# irisc.net
KiCad netlist of a schematic drawn in EAGLE
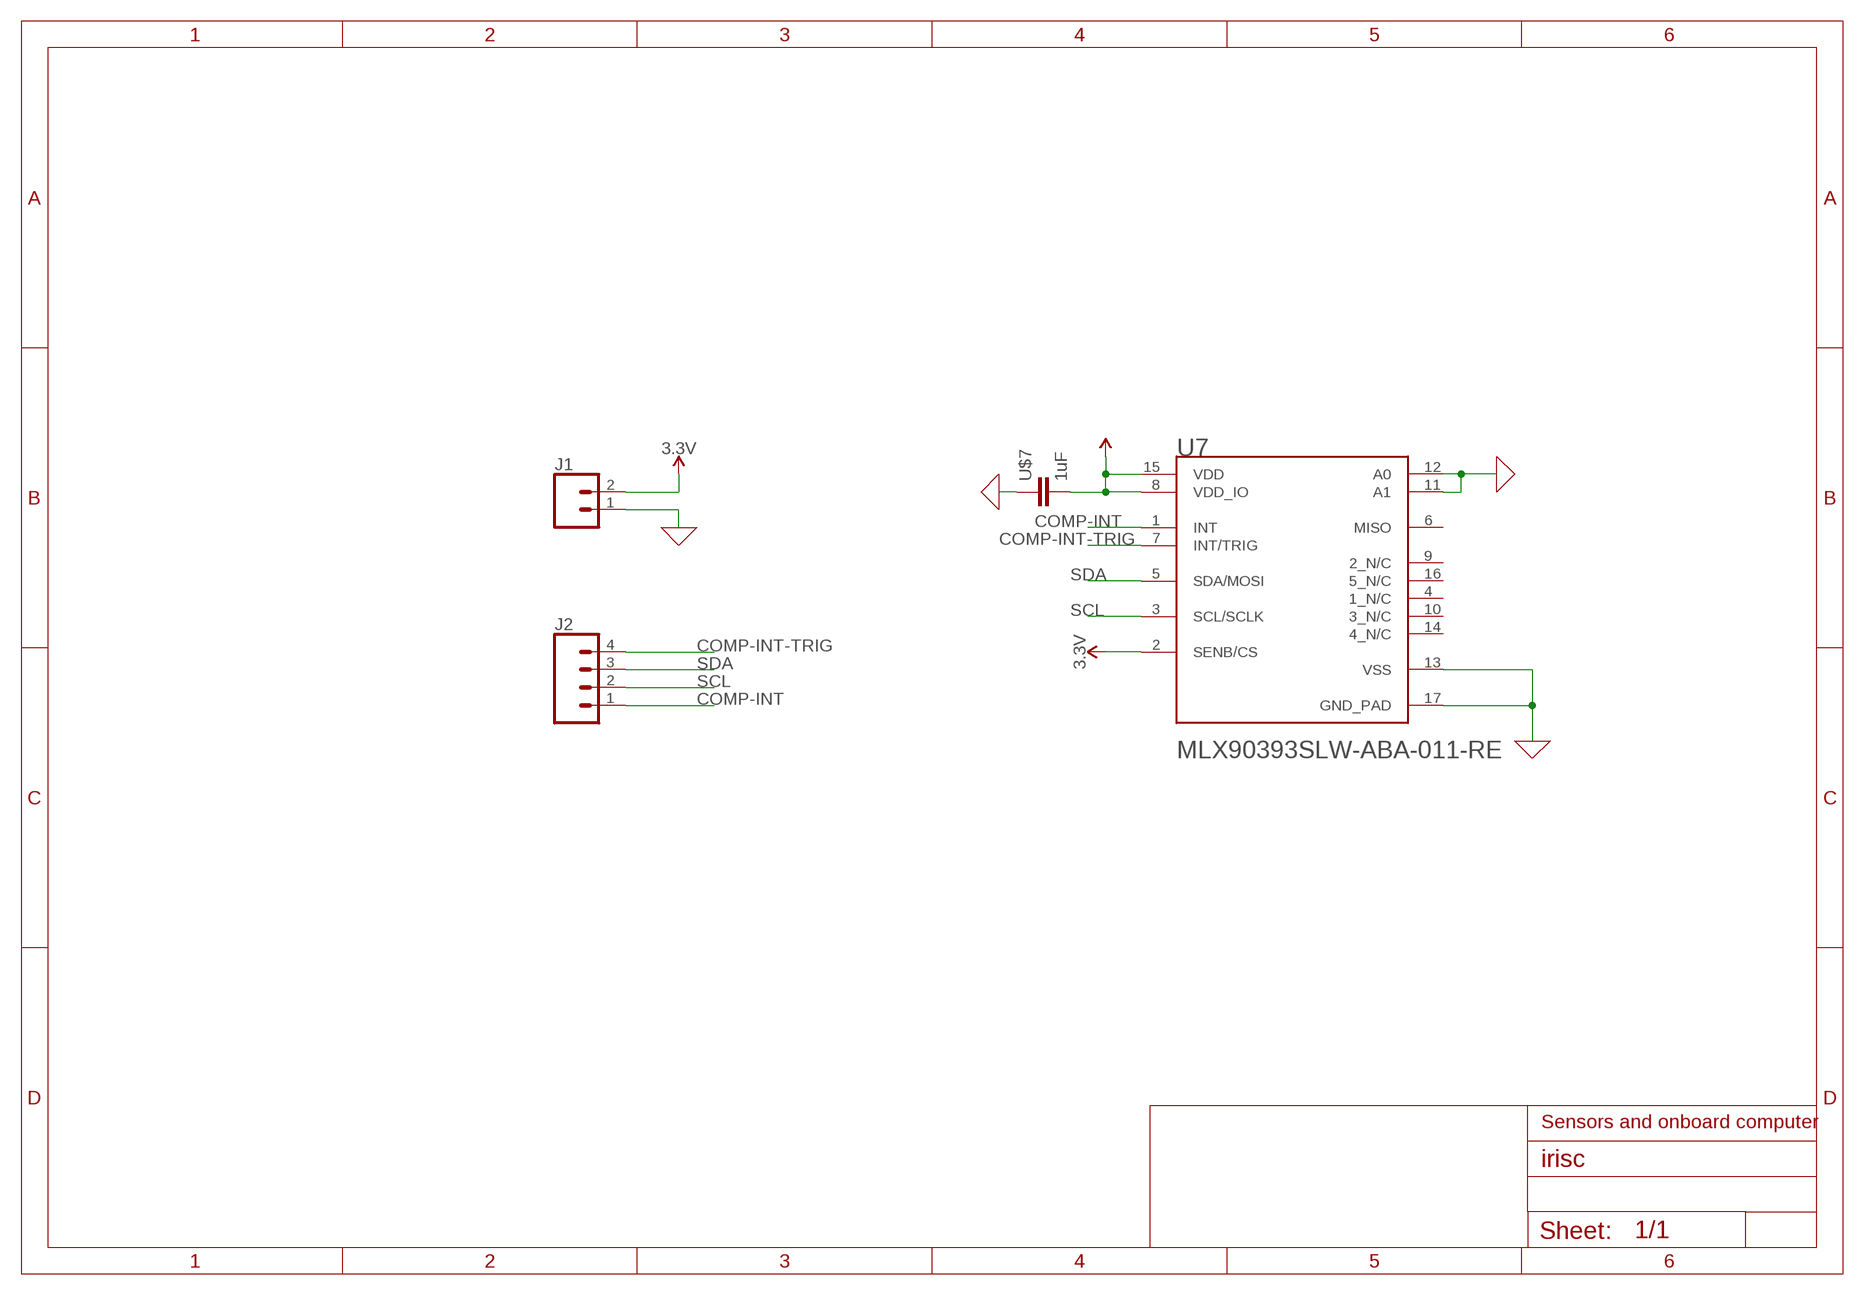
[diagram p0: schematic, sheet 1]

(export (version "E")
  (design (tool "Eeschema 10.0.6"))
  (components
    (comp (ref "J1")
      (value "CONN_02")
      (footprint "eagle-import:1X02")
      (libsource (lib "eagle-import") (part "CONN_02"))
    )
    (comp (ref "J2")
      (value "CONN_04")
      (footprint "eagle-import:1X04")
      (libsource (lib "eagle-import") (part "CONN_04"))
    )
    (comp (ref "U$7")
      (value "1uF")
      (footprint "eagle-import:RESC0603_N")
      (libsource (lib "eagle-import") (part "CAPACITOR_0603_N"))
    )
    (comp (ref "U7")
      (value "MELEXIS_TECHNOLOGIES_MLX90393SLW-ABA-011-REMELEXIS_TECHNOLOGIES_MLX90393SLW-ABA-011-RE_0_0")
      (footprint "eagle-import:MELEXIS_TECHNOLOGIES_MLX90393SLW-ABA-011-RE_0")
      (fields
        (field (name "DIGIKEY_PART_NUMBER") "MLX90393SLW-ABA-011-RECT-ND")
        (field (name "MF") "Melexis Technologies")
        (field (name "MOUSER_PART_NUMBER") "482-90393SLWABA011RE")
      )
      (libsource (lib "eagle-import") (part "MELEXIS_TECHNOLOGIES_MLX90393SLW-ABA-011-REMELEXIS_TECHNOLOGIES_MLX90393SLW-ABA-011-RE_0_0"))
    )
  )
  (nets
    (net (code "1") (name "/COMP-INT") (class "Default")
      (node (ref "J2") (pin "1") (pinfunction "1_1") (pintype "passive"))
      (node (ref "U7") (pin "1") (pinfunction "INT_1") (pintype "bidirectional"))
    )
    (net (code "2") (name "/COMP-INT-TRIG") (class "Default")
      (node (ref "J2") (pin "4") (pinfunction "4_4") (pintype "passive"))
      (node (ref "U7") (pin "7") (pinfunction "INT/TRIG_7") (pintype "bidirectional"))
    )
    (net (code "3") (name "/SCL") (class "Default")
      (node (ref "J2") (pin "2") (pinfunction "2_2") (pintype "passive"))
      (node (ref "U7") (pin "3") (pinfunction "SCL/SCLK_3") (pintype "bidirectional"))
    )
    (net (code "4") (name "/SDA") (class "Default")
      (node (ref "J2") (pin "3") (pinfunction "3_3") (pintype "passive"))
      (node (ref "U7") (pin "5") (pinfunction "SDA/MOSI_5") (pintype "bidirectional"))
    )
    (net (code "5") (name "3.3V") (class "Default")
      (node (ref "J1") (pin "2") (pinfunction "2_2") (pintype "passive"))
      (node (ref "U$7") (pin "2") (pinfunction "2_2") (pintype "passive"))
      (node (ref "U7") (pin "15") (pinfunction "VDD_15") (pintype "bidirectional"))
      (node (ref "U7") (pin "2") (pinfunction "SENB/CS_2") (pintype "bidirectional"))
      (node (ref "U7") (pin "8") (pinfunction "VDD_IO_8") (pintype "bidirectional"))
    )
    (net (code "6") (name "GND") (class "Default")
      (node (ref "J1") (pin "1") (pinfunction "1_1") (pintype "passive"))
      (node (ref "U$7") (pin "1") (pinfunction "1_1") (pintype "passive"))
      (node (ref "U7") (pin "11") (pinfunction "A1_11") (pintype "bidirectional"))
      (node (ref "U7") (pin "12") (pinfunction "A0_12") (pintype "bidirectional"))
      (node (ref "U7") (pin "13") (pinfunction "VSS_13") (pintype "bidirectional"))
      (node (ref "U7") (pin "17") (pinfunction "GND_PAD_17") (pintype "bidirectional"))
    )
    (net (code "7") (name "unconnected-(U7-1_N{slash}C-Pad4)") (class "Default")
      (node (ref "U7") (pin "4") (pinfunction "1_N/C_4") (pintype "bidirectional"))
    )
    (net (code "8") (name "unconnected-(U7-2_N{slash}C-Pad9)") (class "Default")
      (node (ref "U7") (pin "9") (pinfunction "2_N/C_9") (pintype "bidirectional"))
    )
    (net (code "9") (name "unconnected-(U7-3_N{slash}C-Pad10)") (class "Default")
      (node (ref "U7") (pin "10") (pinfunction "3_N/C_10") (pintype "bidirectional"))
    )
    (net (code "10") (name "unconnected-(U7-4_N{slash}C-Pad14)") (class "Default")
      (node (ref "U7") (pin "14") (pinfunction "4_N/C_14") (pintype "bidirectional"))
    )
    (net (code "11") (name "unconnected-(U7-5_N{slash}C-Pad16)") (class "Default")
      (node (ref "U7") (pin "16") (pinfunction "5_N/C_16") (pintype "bidirectional"))
    )
    (net (code "12") (name "unconnected-(U7-MISO-Pad6)") (class "Default")
      (node (ref "U7") (pin "6") (pinfunction "MISO_6") (pintype "bidirectional"))
    )
  )
)
